# extrasheet.net
KiCad netlist of a schematic drawn in Altium Designer
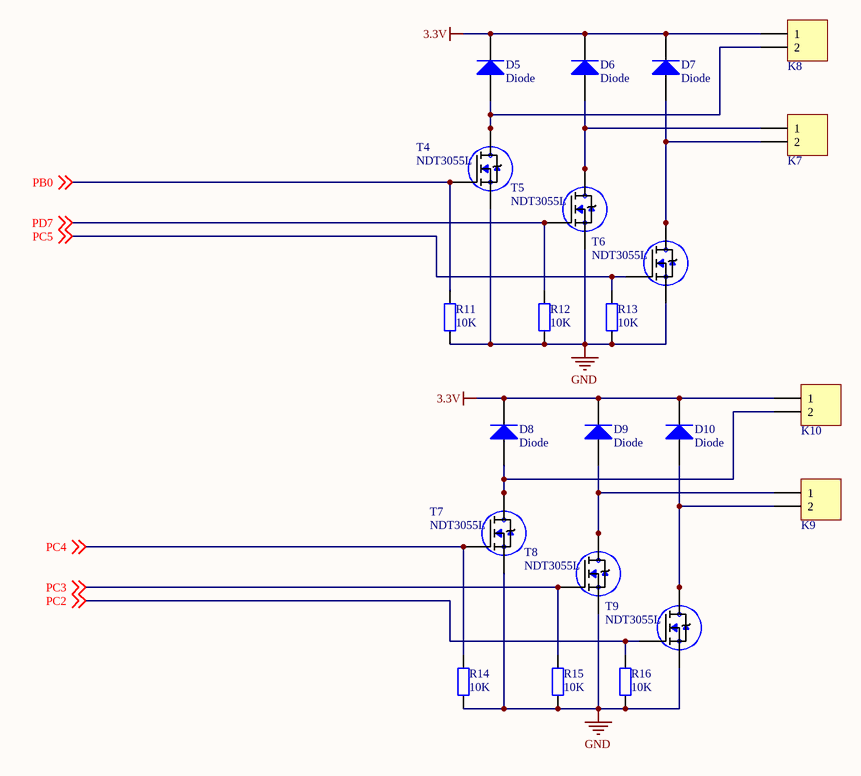
[diagram p0: extrasheet.SchDoc]

(export (version "E")
  (design (tool "Eeschema 10.0.6"))
  (components
    (comp (ref "D5")
      (value "Diode")
      (footprint "Diode")
      (description "Default Diode")
      (fields (field (name "PUBLISHER") "Altium Limited"))
      (libsource (lib "Miscellaneous Devices") (part "Diode"))
    )
    (comp (ref "D6")
      (value "Diode")
      (footprint "Diode")
      (description "Default Diode")
      (fields (field (name "PUBLISHER") "Altium Limited"))
      (libsource (lib "Miscellaneous Devices") (part "Diode"))
    )
    (comp (ref "D7")
      (value "Diode")
      (footprint "Diode")
      (description "Default Diode")
      (fields (field (name "PUBLISHER") "Altium Limited"))
      (libsource (lib "Miscellaneous Devices") (part "Diode"))
    )
    (comp (ref "D8")
      (value "Diode")
      (footprint "Diode")
      (description "Default Diode")
      (fields (field (name "PUBLISHER") "Altium Limited"))
      (libsource (lib "Miscellaneous Devices") (part "Diode"))
    )
    (comp (ref "D9")
      (value "Diode")
      (footprint "Diode")
      (description "Default Diode")
      (fields (field (name "PUBLISHER") "Altium Limited"))
      (libsource (lib "Miscellaneous Devices") (part "Diode"))
    )
    (comp (ref "D10")
      (value "Diode")
      (footprint "Diode")
      (description "Default Diode")
      (fields (field (name "PUBLISHER") "Altium Limited"))
      (libsource (lib "Miscellaneous Devices") (part "Diode"))
    )
    (comp (ref "K7")
      (value "K7")
      (footprint "K12")
      (description "Header, 2-Pin")
      (fields (field (name "PUBLISHER") "Altium Limited"))
      (libsource (lib "Miscellaneous Connectors") (part "Header 2"))
    )
    (comp (ref "K8")
      (value "K8")
      (footprint "K12")
      (description "Header, 2-Pin")
      (fields (field (name "PUBLISHER") "Altium Limited"))
      (libsource (lib "Miscellaneous Connectors") (part "Header 2"))
    )
    (comp (ref "K9")
      (value "K9")
      (footprint "K12")
      (description "Header, 2-Pin")
      (fields (field (name "PUBLISHER") "Altium Limited"))
      (libsource (lib "Miscellaneous Connectors") (part "Header 2"))
    )
    (comp (ref "K10")
      (value "K10")
      (footprint "K12")
      (description "Header, 2-Pin")
      (fields (field (name "PUBLISHER") "Altium Limited"))
      (libsource (lib "Miscellaneous Connectors") (part "Header 2"))
    )
    (comp (ref "R11")
      (value "10K")
      (footprint "C13+R")
      (description "Resistor")
      (fields (field (name "Comment") "Res2") (field (name "PUBLISHER") "Altium Limited"))
      (libsource (lib "") (part "Res2_1"))
    )
    (comp (ref "R12")
      (value "10K")
      (footprint "C13+R")
      (description "Resistor")
      (fields (field (name "Comment") "Res2") (field (name "PUBLISHER") "Altium Limited"))
      (libsource (lib "Miscellaneous Devices") (part "Res2"))
    )
    (comp (ref "R13")
      (value "10K")
      (footprint "C13+R")
      (description "Resistor")
      (fields (field (name "Comment") "Res2") (field (name "PUBLISHER") "Altium Limited"))
      (libsource (lib "Miscellaneous Devices") (part "Res2"))
    )
    (comp (ref "R14")
      (value "10K")
      (footprint "C13+R")
      (description "Resistor")
      (fields (field (name "Comment") "Res2") (field (name "PUBLISHER") "Altium Limited"))
      (libsource (lib "") (part "Res2_1"))
    )
    (comp (ref "R15")
      (value "10K")
      (footprint "C13+R")
      (description "Resistor")
      (fields (field (name "Comment") "Res2") (field (name "PUBLISHER") "Altium Limited"))
      (libsource (lib "Miscellaneous Devices") (part "Res2"))
    )
    (comp (ref "R16")
      (value "10K")
      (footprint "C13+R")
      (description "Resistor")
      (fields (field (name "Comment") "Res2") (field (name "PUBLISHER") "Altium Limited"))
      (libsource (lib "Miscellaneous Devices") (part "Res2"))
    )
    (comp (ref "T4")
      (value "NDT3055L")
      (footprint "*SOT223-4")
      (libsource (lib "NDT3055L") (part "NDT3055L"))
    )
    (comp (ref "T5")
      (value "NDT3055L")
      (footprint "*SOT223-4")
      (libsource (lib "NDT3055L") (part "NDT3055L"))
    )
    (comp (ref "T6")
      (value "NDT3055L")
      (footprint "*SOT223-4")
      (libsource (lib "NDT3055L") (part "NDT3055L"))
    )
    (comp (ref "T7")
      (value "NDT3055L")
      (footprint "*SOT223-4")
      (libsource (lib "NDT3055L") (part "NDT3055L"))
    )
    (comp (ref "T8")
      (value "NDT3055L")
      (footprint "*SOT223-4")
      (libsource (lib "NDT3055L") (part "NDT3055L"))
    )
    (comp (ref "T9")
      (value "NDT3055L")
      (footprint "*SOT223-4")
      (libsource (lib "NDT3055L") (part "NDT3055L"))
    )
  )
  (nets
    (net (code "1") (name "3.3V") (class "Default")
      (node (ref "D10") (pin "K") (pinfunction "K_K") (pintype "passive"))
      (node (ref "D5") (pin "K") (pinfunction "K_K") (pintype "passive"))
      (node (ref "D6") (pin "K") (pinfunction "K_K") (pintype "passive"))
      (node (ref "D7") (pin "K") (pinfunction "K_K") (pintype "passive"))
      (node (ref "D8") (pin "K") (pinfunction "K_K") (pintype "passive"))
      (node (ref "D9") (pin "K") (pinfunction "K_K") (pintype "passive"))
      (node (ref "K10") (pin "1") (pinfunction "1_1") (pintype "passive"))
      (node (ref "K8") (pin "1") (pinfunction "1_1") (pintype "passive"))
    )
    (net (code "2") (name "GND") (class "Default")
      (node (ref "R11") (pin "2") (pinfunction "2_2") (pintype "passive"))
      (node (ref "R12") (pin "1") (pinfunction "1_1") (pintype "passive"))
      (node (ref "R13") (pin "1") (pinfunction "1_1") (pintype "passive"))
      (node (ref "R14") (pin "2") (pinfunction "2_2") (pintype "passive"))
      (node (ref "R15") (pin "1") (pinfunction "1_1") (pintype "passive"))
      (node (ref "R16") (pin "1") (pinfunction "1_1") (pintype "passive"))
      (node (ref "T4") (pin "3") (pinfunction "S_3") (pintype "passive"))
      (node (ref "T5") (pin "3") (pinfunction "S_3") (pintype "passive"))
      (node (ref "T6") (pin "3") (pinfunction "S_3") (pintype "passive"))
      (node (ref "T7") (pin "3") (pinfunction "S_3") (pintype "passive"))
      (node (ref "T8") (pin "3") (pinfunction "S_3") (pintype "passive"))
      (node (ref "T9") (pin "3") (pinfunction "S_3") (pintype "passive"))
    )
    (net (code "3") (name "Net-(D5-PadA)") (class "Default")
      (node (ref "D5") (pin "A") (pinfunction "A_A") (pintype "passive"))
      (node (ref "K8") (pin "2") (pinfunction "2_2") (pintype "passive"))
      (node (ref "T4") (pin "2") (pinfunction "D_2") (pintype "passive"))
      (node (ref "T4") (pin "4") (pinfunction "D_4") (pintype "passive"))
    )
    (net (code "4") (name "Net-(D6-PadA)") (class "Default")
      (node (ref "D6") (pin "A") (pinfunction "A_A") (pintype "passive"))
      (node (ref "K7") (pin "1") (pinfunction "1_1") (pintype "passive"))
      (node (ref "T5") (pin "2") (pinfunction "D_2") (pintype "passive"))
      (node (ref "T5") (pin "4") (pinfunction "D_4") (pintype "passive"))
    )
    (net (code "5") (name "Net-(D7-PadA)") (class "Default")
      (node (ref "D7") (pin "A") (pinfunction "A_A") (pintype "passive"))
      (node (ref "K7") (pin "2") (pinfunction "2_2") (pintype "passive"))
      (node (ref "T6") (pin "2") (pinfunction "D_2") (pintype "passive"))
      (node (ref "T6") (pin "4") (pinfunction "D_4") (pintype "passive"))
    )
    (net (code "6") (name "Net-(D8-PadA)") (class "Default")
      (node (ref "D8") (pin "A") (pinfunction "A_A") (pintype "passive"))
      (node (ref "K10") (pin "2") (pinfunction "2_2") (pintype "passive"))
      (node (ref "T7") (pin "2") (pinfunction "D_2") (pintype "passive"))
      (node (ref "T7") (pin "4") (pinfunction "D_4") (pintype "passive"))
    )
    (net (code "7") (name "Net-(D9-PadA)") (class "Default")
      (node (ref "D9") (pin "A") (pinfunction "A_A") (pintype "passive"))
      (node (ref "K9") (pin "1") (pinfunction "1_1") (pintype "passive"))
      (node (ref "T8") (pin "2") (pinfunction "D_2") (pintype "passive"))
      (node (ref "T8") (pin "4") (pinfunction "D_4") (pintype "passive"))
    )
    (net (code "8") (name "Net-(D10-PadA)") (class "Default")
      (node (ref "D10") (pin "A") (pinfunction "A_A") (pintype "passive"))
      (node (ref "K9") (pin "2") (pinfunction "2_2") (pintype "passive"))
      (node (ref "T9") (pin "2") (pinfunction "D_2") (pintype "passive"))
      (node (ref "T9") (pin "4") (pinfunction "D_4") (pintype "passive"))
    )
    (net (code "9") (name "PB0") (class "Default")
      (node (ref "R11") (pin "1") (pinfunction "1_1") (pintype "passive"))
      (node (ref "T4") (pin "1") (pinfunction "G_1") (pintype "passive"))
    )
    (net (code "10") (name "PC2") (class "Default")
      (node (ref "R16") (pin "2") (pinfunction "2_2") (pintype "passive"))
      (node (ref "T9") (pin "1") (pinfunction "G_1") (pintype "passive"))
    )
    (net (code "11") (name "PC3") (class "Default")
      (node (ref "R15") (pin "2") (pinfunction "2_2") (pintype "passive"))
      (node (ref "T8") (pin "1") (pinfunction "G_1") (pintype "passive"))
    )
    (net (code "12") (name "PC4") (class "Default")
      (node (ref "R14") (pin "1") (pinfunction "1_1") (pintype "passive"))
      (node (ref "T7") (pin "1") (pinfunction "G_1") (pintype "passive"))
    )
    (net (code "13") (name "PC5") (class "Default")
      (node (ref "R13") (pin "2") (pinfunction "2_2") (pintype "passive"))
      (node (ref "T6") (pin "1") (pinfunction "G_1") (pintype "passive"))
    )
    (net (code "14") (name "PD7") (class "Default")
      (node (ref "R12") (pin "2") (pinfunction "2_2") (pintype "passive"))
      (node (ref "T5") (pin "1") (pinfunction "G_1") (pintype "passive"))
    )
  )
)
